# MAX30101_Qwiic_PCB_v6.net
KiCad netlist of a schematic drawn in EAGLE
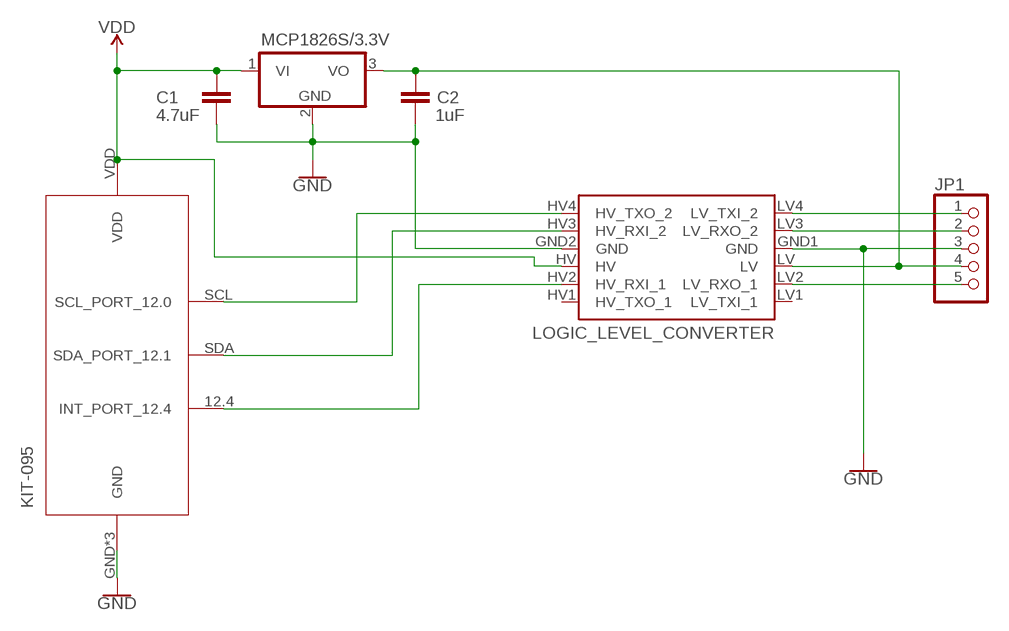
[diagram p0: schematic, sheet 1]

(export (version "E")
  (design (tool "Eeschema 10.0.6"))
  (components
    (comp (ref "C1")
      (value "4.7uF")
      (footprint "eagle-import:CAP-PTH-SMALL-KIT")
      (libsource (lib "eagle-import") (part "0.1UF-KIT-EZ-50V-20%"))
    )
    (comp (ref "C2")
      (value "1uF")
      (footprint "eagle-import:CAP-PTH-SMALL-KIT")
      (libsource (lib "eagle-import") (part "0.1UF-KIT-EZ-50V-20%"))
    )
    (comp (ref "IC1")
      (value "7805T")
      (footprint "eagle-import:TO220H")
      (libsource (lib "eagle-import") (part "78T05"))
    )
    (comp (ref "JP1")
      (value "PINHD-1X5/90")
      (footprint "eagle-import:1X05_90")
      (libsource (lib "eagle-import") (part "PINHD-1X5/90"))
    )
    (comp (ref "KIT-095")
      (value "KIT-095")
      (footprint "eagle-import:KIT-095")
      (libsource (lib "eagle-import") (part "KIT-095"))
    )
    (comp (ref "LOGIC_LEVEL_CONVERTER")
      (value "SPARKFUN_LOGIC_LEVEL_CONVERTER")
      (footprint "eagle-import:SPARKFUN_LOGIC_LEVEL_CONVERTER")
      (libsource (lib "eagle-import") (part "SPARKFUN_LOGIC_LEVEL_CONVERTER"))
    )
  )
  (nets
    (net (code "1") (name "GND") (class "Default")
      (node (ref "C1") (pin "2") (pinfunction "2_2") (pintype "passive"))
      (node (ref "C2") (pin "2") (pinfunction "2_2") (pintype "passive"))
      (node (ref "IC1") (pin "2") (pinfunction "GND_2") (pintype "passive"))
      (node (ref "JP1") (pin "3") (pinfunction "3_3") (pintype "passive"))
      (node (ref "KIT-095") (pin "GND") (pinfunction "GND_GND") (pintype "power_in"))
      (node (ref "KIT-095") (pin "GND_") (pinfunction "GND_GND_") (pintype "power_in"))
      (node (ref "KIT-095") (pin "_GND") (pinfunction "GND__GND") (pintype "power_in"))
      (node (ref "LOGIC_LEVEL_CONVERTER") (pin "GND1") (pinfunction "GND_GND1") (pintype "power_in"))
      (node (ref "LOGIC_LEVEL_CONVERTER") (pin "GND2") (pinfunction "GND_GND2") (pintype "power_in"))
    )
    (net (code "2") (name "Net-(IC1-VO)") (class "Default")
      (node (ref "C2") (pin "1") (pinfunction "1_1") (pintype "passive"))
      (node (ref "IC1") (pin "3") (pinfunction "VO_3") (pintype "passive"))
      (node (ref "JP1") (pin "4") (pinfunction "4_4") (pintype "passive"))
      (node (ref "LOGIC_LEVEL_CONVERTER") (pin "LV") (pinfunction "LV_LV") (pintype "power_in"))
    )
    (net (code "3") (name "Net-(KIT-095-INT_PORT_12.4)") (class "Default")
      (node (ref "KIT-095") (pin "12.4") (pinfunction "INT_PORT_12.4_12.4") (pintype "bidirectional"))
      (node (ref "LOGIC_LEVEL_CONVERTER") (pin "HV2") (pinfunction "HV_RXI_1_HV2") (pintype "bidirectional"))
    )
    (net (code "4") (name "Net-(KIT-095-SCL_PORT_12.0)") (class "Default")
      (node (ref "KIT-095") (pin "SCL") (pinfunction "SCL_PORT_12.0_SCL") (pintype "bidirectional"))
      (node (ref "LOGIC_LEVEL_CONVERTER") (pin "HV4") (pinfunction "HV_TXO_2_HV4") (pintype "bidirectional"))
    )
    (net (code "5") (name "Net-(KIT-095-SDA_PORT_12.1)") (class "Default")
      (node (ref "KIT-095") (pin "SDA") (pinfunction "SDA_PORT_12.1_SDA") (pintype "bidirectional"))
      (node (ref "LOGIC_LEVEL_CONVERTER") (pin "HV3") (pinfunction "HV_RXI_2_HV3") (pintype "bidirectional"))
    )
    (net (code "6") (name "Net-(LOGIC_LEVEL_CONVERTER-LV_RXO_1)") (class "Default")
      (node (ref "JP1") (pin "5") (pinfunction "5_5") (pintype "passive"))
      (node (ref "LOGIC_LEVEL_CONVERTER") (pin "LV2") (pinfunction "LV_RXO_1_LV2") (pintype "bidirectional"))
    )
    (net (code "7") (name "Net-(LOGIC_LEVEL_CONVERTER-LV_RXO_2)") (class "Default")
      (node (ref "JP1") (pin "2") (pinfunction "2_2") (pintype "passive"))
      (node (ref "LOGIC_LEVEL_CONVERTER") (pin "LV3") (pinfunction "LV_RXO_2_LV3") (pintype "bidirectional"))
    )
    (net (code "8") (name "Net-(LOGIC_LEVEL_CONVERTER-LV_TXI_2)") (class "Default")
      (node (ref "JP1") (pin "1") (pinfunction "1_1") (pintype "passive"))
      (node (ref "LOGIC_LEVEL_CONVERTER") (pin "LV4") (pinfunction "LV_TXI_2_LV4") (pintype "bidirectional"))
    )
    (net (code "9") (name "VDD") (class "Default")
      (node (ref "C1") (pin "1") (pinfunction "1_1") (pintype "passive"))
      (node (ref "IC1") (pin "1") (pinfunction "VI_1") (pintype "input"))
      (node (ref "KIT-095") (pin "VDD") (pinfunction "VDD_VDD") (pintype "power_in"))
      (node (ref "LOGIC_LEVEL_CONVERTER") (pin "HV") (pinfunction "HV_HV") (pintype "power_in"))
    )
    (net (code "10") (name "unconnected-(LOGIC_LEVEL_CONVERTER-HV_TXO_1-PadHV1)") (class "Default")
      (node (ref "LOGIC_LEVEL_CONVERTER") (pin "HV1") (pinfunction "HV_TXO_1_HV1") (pintype "bidirectional"))
    )
    (net (code "11") (name "unconnected-(LOGIC_LEVEL_CONVERTER-LV_TXI_1-PadLV1)") (class "Default")
      (node (ref "LOGIC_LEVEL_CONVERTER") (pin "LV1") (pinfunction "LV_TXI_1_LV1") (pintype "bidirectional"))
    )
  )
)
